# USB-UART_Driver.net
KiCad netlist of a schematic drawn in Altium Designer
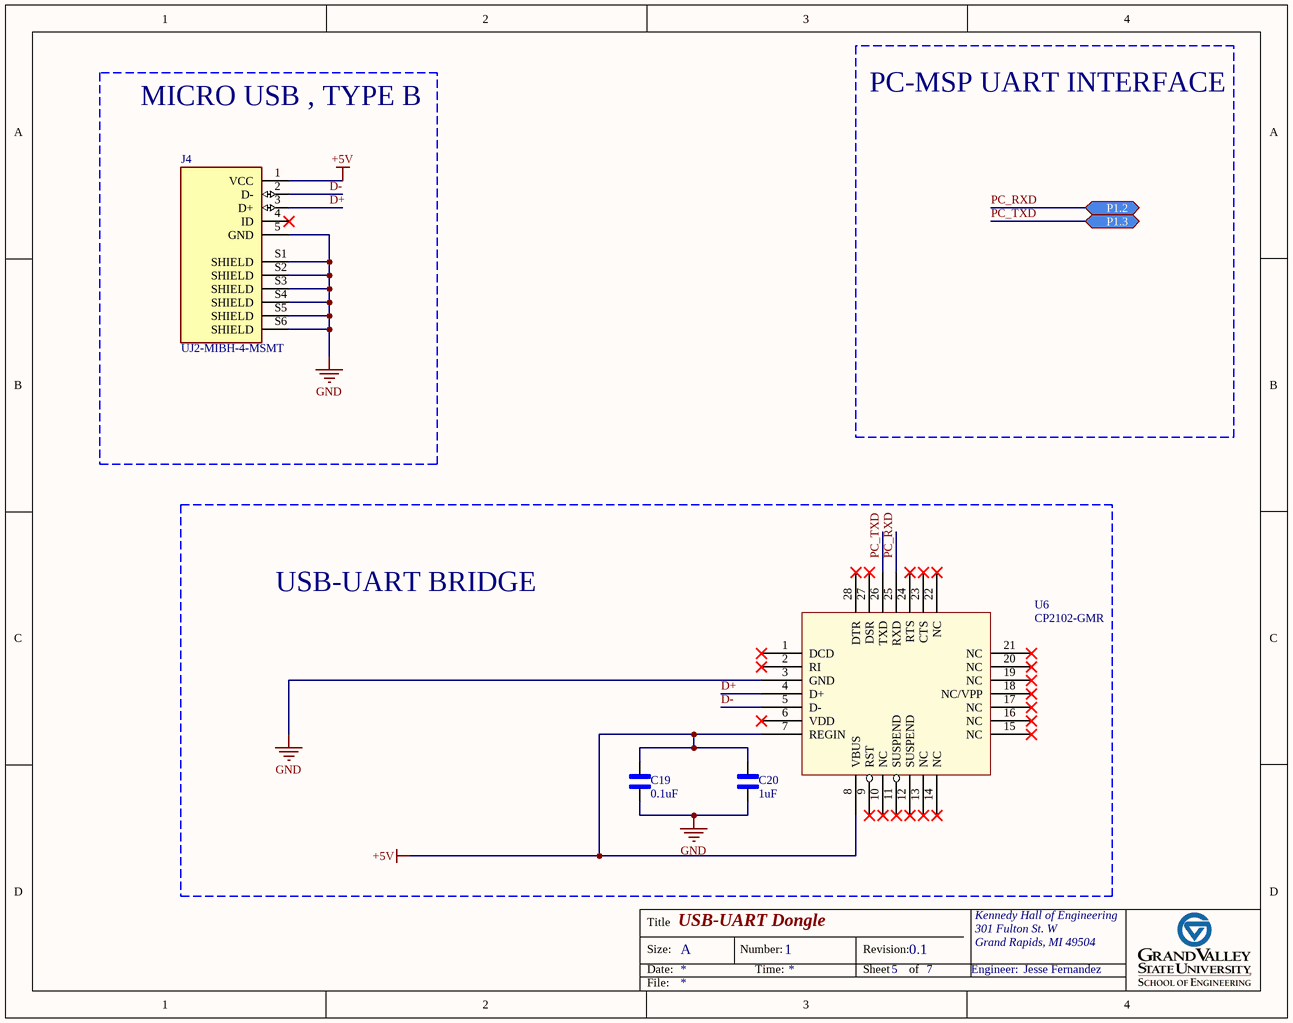
[diagram p0: USB-UART Driver.SchDoc]

(export (version "E")
  (design (tool "Eeschema 10.0.6"))
  (components
    (comp (ref "C19")
      (value "0.1uF")
      (footprint "CAPC1005X55N")
      (description "Capacitor X6S 0402 (1005 Metric)")
      (fields (field (name "MANUFACTURER") "Murata Electronics") (field (name "TOLERANCE") "10%"))
      (libsource (lib "UngBung") (part "Multilayer Ceramic Cap. 0402 (1005 Metric)"))
    )
    (comp (ref "C20")
      (value "1uF")
      (footprint "CAPC1005X55N")
      (description "Capacitor X6S 0402 (1005 Metric)")
      (fields (field (name "MANUFACTURER") "Murata Electronics") (field (name "TOLERANCE") "10%"))
      (libsource (lib "UngBung") (part "Multilayer Ceramic Cap. 0402 (1005 Metric)"))
    )
    (comp (ref "J4")
      (value "UJ2-MIBH-4-MSMT")
      (footprint "UJ2-MIBH-4-MSMT")
      (description "USB Connectors USB 2.0 micro B jack 5 pin HZ mid-mnt SMT")
      (fields (field (name "MANUFACTURER") "CUI Devices"))
      (libsource (lib "UngBung") (part "UJ2-MIBH-4-MSMT"))
    )
    (comp (ref "U6")
      (value "CP2102-GMR")
      (footprint "CP2102-GMR")
      (description "USB Bridge, USB to UART USB 2.0 UART Interface 28-QFN (5x5)")
      (fields (field (name "MANUFACTURER") "Silicon Labs"))
      (libsource (lib "UngBung") (part "CP2102-GMR"))
    )
  )
  (nets
    (net (code "1") (name "+5V") (class "Default")
      (node (ref "C19") (pin "2") (pinfunction "2_2") (pintype "passive"))
      (node (ref "C20") (pin "2") (pinfunction "2_2") (pintype "passive"))
      (node (ref "J4") (pin "1") (pinfunction "VCC_1") (pintype "power_in"))
      (node (ref "U6") (pin "7") (pinfunction "REGIN_7") (pintype "passive"))
      (node (ref "U6") (pin "8") (pinfunction "VBUS_8") (pintype "passive"))
    )
    (net (code "2") (name "/D+") (class "Default")
      (node (ref "J4") (pin "3") (pinfunction "D+_3") (pintype "bidirectional"))
      (node (ref "U6") (pin "4") (pinfunction "D+_4") (pintype "passive"))
    )
    (net (code "3") (name "/D-") (class "Default")
      (node (ref "J4") (pin "2") (pinfunction "D-_2") (pintype "bidirectional"))
      (node (ref "U6") (pin "5") (pinfunction "D-_5") (pintype "passive"))
    )
    (net (code "4") (name "/PC_RXD") (class "Default")
      (node (ref "U6") (pin "25") (pinfunction "RXD_25") (pintype "passive"))
    )
    (net (code "5") (name "/PC_TXD") (class "Default")
      (node (ref "U6") (pin "26") (pinfunction "TXD_26") (pintype "passive"))
    )
    (net (code "6") (name "GND") (class "Default")
      (node (ref "C19") (pin "1") (pinfunction "1_1") (pintype "passive"))
      (node (ref "C20") (pin "1") (pinfunction "1_1") (pintype "passive"))
      (node (ref "J4") (pin "5") (pinfunction "GND_5") (pintype "power_in"))
      (node (ref "J4") (pin "S1") (pinfunction "SHIELD_S1") (pintype "passive"))
      (node (ref "J4") (pin "S2") (pinfunction "SHIELD_S2") (pintype "passive"))
      (node (ref "J4") (pin "S3") (pinfunction "SHIELD_S3") (pintype "passive"))
      (node (ref "J4") (pin "S4") (pinfunction "SHIELD_S4") (pintype "passive"))
      (node (ref "J4") (pin "S5") (pinfunction "SHIELD_S5") (pintype "passive"))
      (node (ref "J4") (pin "S6") (pinfunction "SHIELD_S6") (pintype "passive"))
      (node (ref "U6") (pin "3") (pinfunction "GND_3") (pintype "passive"))
    )
    (net (code "7") (name "unconnected-(J4-ID-Pad4)") (class "Default")
      (node (ref "J4") (pin "4") (pinfunction "ID_4") (pintype "passive+no_connect"))
    )
    (net (code "8") (name "unconnected-(U6-CTS-Pad23)") (class "Default")
      (node (ref "U6") (pin "23") (pinfunction "CTS_23") (pintype "passive+no_connect"))
    )
    (net (code "9") (name "unconnected-(U6-DCD-Pad1)") (class "Default")
      (node (ref "U6") (pin "1") (pinfunction "DCD_1") (pintype "passive+no_connect"))
    )
    (net (code "10") (name "unconnected-(U6-DSR-Pad27)") (class "Default")
      (node (ref "U6") (pin "27") (pinfunction "DSR_27") (pintype "passive+no_connect"))
    )
    (net (code "11") (name "unconnected-(U6-DTR-Pad28)") (class "Default")
      (node (ref "U6") (pin "28") (pinfunction "DTR_28") (pintype "passive+no_connect"))
    )
    (net (code "12") (name "unconnected-(U6-NC-Pad10)") (class "Default")
      (node (ref "U6") (pin "10") (pinfunction "NC_10") (pintype "passive+no_connect"))
    )
    (net (code "13") (name "unconnected-(U6-NC-Pad13)") (class "Default")
      (node (ref "U6") (pin "13") (pinfunction "NC_13") (pintype "passive+no_connect"))
    )
    (net (code "14") (name "unconnected-(U6-NC-Pad14)") (class "Default")
      (node (ref "U6") (pin "14") (pinfunction "NC_14") (pintype "passive+no_connect"))
    )
    (net (code "15") (name "unconnected-(U6-NC-Pad15)") (class "Default")
      (node (ref "U6") (pin "15") (pinfunction "NC_15") (pintype "passive+no_connect"))
    )
    (net (code "16") (name "unconnected-(U6-NC-Pad16)") (class "Default")
      (node (ref "U6") (pin "16") (pinfunction "NC_16") (pintype "passive+no_connect"))
    )
    (net (code "17") (name "unconnected-(U6-NC-Pad17)") (class "Default")
      (node (ref "U6") (pin "17") (pinfunction "NC_17") (pintype "passive+no_connect"))
    )
    (net (code "18") (name "unconnected-(U6-NC-Pad19)") (class "Default")
      (node (ref "U6") (pin "19") (pinfunction "NC_19") (pintype "passive+no_connect"))
    )
    (net (code "19") (name "unconnected-(U6-NC-Pad20)") (class "Default")
      (node (ref "U6") (pin "20") (pinfunction "NC_20") (pintype "passive+no_connect"))
    )
    (net (code "20") (name "unconnected-(U6-NC-Pad21)") (class "Default")
      (node (ref "U6") (pin "21") (pinfunction "NC_21") (pintype "passive+no_connect"))
    )
    (net (code "21") (name "unconnected-(U6-NC-Pad22)") (class "Default")
      (node (ref "U6") (pin "22") (pinfunction "NC_22") (pintype "passive+no_connect"))
    )
    (net (code "22") (name "unconnected-(U6-NC{slash}VPP-Pad18)") (class "Default")
      (node (ref "U6") (pin "18") (pinfunction "NC/VPP_18") (pintype "passive+no_connect"))
    )
    (net (code "23") (name "unconnected-(U6-RI-Pad2)") (class "Default")
      (node (ref "U6") (pin "2") (pinfunction "RI_2") (pintype "passive+no_connect"))
    )
    (net (code "24") (name "unconnected-(U6-RST-Pad9)") (class "Default")
      (node (ref "U6") (pin "9") (pinfunction "RST_9") (pintype "passive+no_connect"))
    )
    (net (code "25") (name "unconnected-(U6-RTS-Pad24)") (class "Default")
      (node (ref "U6") (pin "24") (pinfunction "RTS_24") (pintype "passive+no_connect"))
    )
    (net (code "26") (name "unconnected-(U6-SUSPEND-Pad11)") (class "Default")
      (node (ref "U6") (pin "11") (pinfunction "SUSPEND_11") (pintype "passive+no_connect"))
    )
    (net (code "27") (name "unconnected-(U6-SUSPEND-Pad12)") (class "Default")
      (node (ref "U6") (pin "12") (pinfunction "SUSPEND_12") (pintype "passive+no_connect"))
    )
    (net (code "28") (name "unconnected-(U6-VDD-Pad6)") (class "Default")
      (node (ref "U6") (pin "6") (pinfunction "VDD_6") (pintype "passive+no_connect"))
    )
  )
)
